# Antennas.net
KiCad netlist of a schematic drawn in Altium Designer
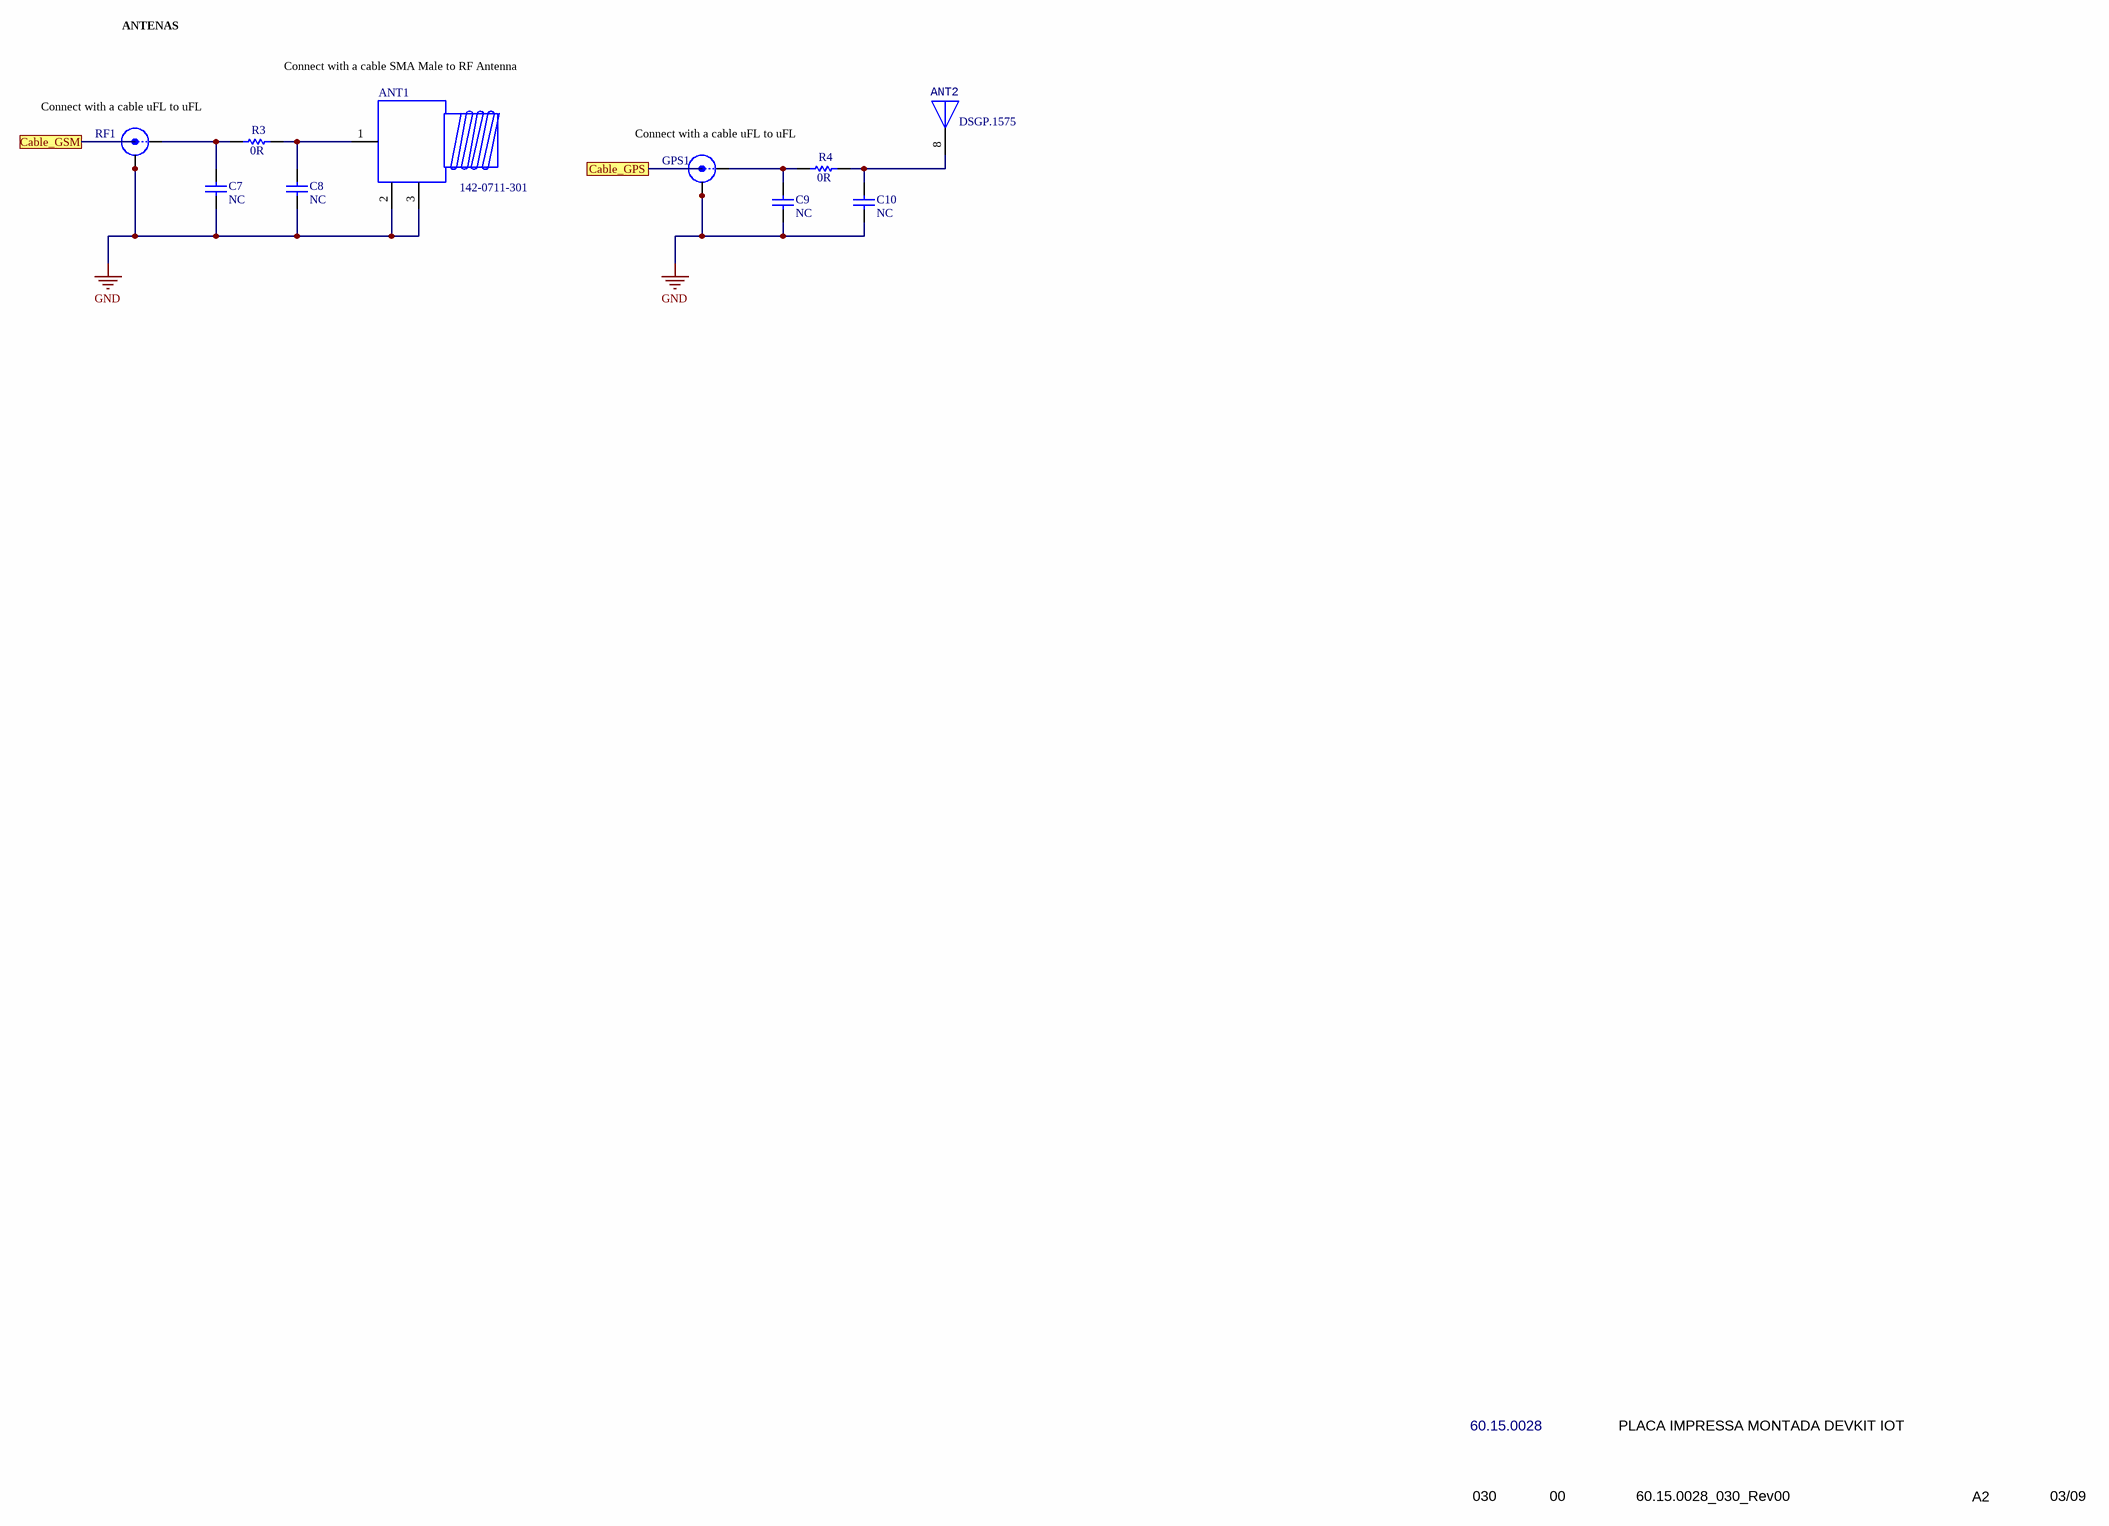
[diagram p0: Antennas.SchDoc]

(export (version "E")
  (design (tool "Eeschema 10.0.6"))
  (components
    (comp (ref "ANT1")
      (value "142-0711-301")
      (footprint "28.21.0036")
      (description "CONECTOR SMA JACK R/A 50 OHM SMD")
      (fields (field (name "Comment") "28.21.0036"))
      (libsource (lib "OMNI-CONECTORES") (part "28.21.0036"))
    )
    (comp (ref "ANT2")
      (value "50.42.0045")
      (footprint "50.42.0045")
      (description "ANTENA CERAMICA SMT PARA GPSL1")
      (fields (field (name "ALTIUM_UNNAMED_1") "DSGP.1575"))
      (libsource (lib "OMNI-COMP-RF") (part "50.42.0045"))
    )
    (comp (ref "C7")
      (value "NC")
      (footprint "0603-CAP-NA")
      (description "CAPACITOR ABERTO")
      (fields (field (name "Comment") "0603-CAP-NA"))
      (libsource (lib "OMNI-SEM-COD") (part "0603-CAP-NA"))
    )
    (comp (ref "C8")
      (value "NC")
      (footprint "0603-CAP-NA")
      (description "CAPACITOR ABERTO")
      (fields (field (name "Comment") "0603-CAP-NA"))
      (libsource (lib "OMNI-SEM-COD") (part "0603-CAP-NA"))
    )
    (comp (ref "C9")
      (value "NC")
      (footprint "0603-CAP-NA")
      (description "CAPACITOR ABERTO")
      (fields (field (name "Comment") "0603-CAP-NA"))
      (libsource (lib "OMNI-SEM-COD") (part "0603-CAP-NA"))
    )
    (comp (ref "C10")
      (value "NC")
      (footprint "0603-CAP-NA")
      (description "CAPACITOR ABERTO")
      (fields (field (name "Comment") "0603-CAP-NA"))
      (libsource (lib "OMNI-SEM-COD") (part "0603-CAP-NA"))
    )
    (comp (ref "GPS1")
      (value "28.20.0019")
      (footprint "28.20.0019")
      (description "CONECTOR MICRO COAXIAL 50 OHM SMD")
      (libsource (lib "OMNI-CONECTORES") (part "28.20.0019"))
    )
    (comp (ref "R3")
      (value "0R")
      (footprint "66.24.1337")
      (description "RESISTOR THICK FILM 0,1W 0 OHMS SMD 0603")
      (fields (field (name "Comment") "66.24.1337"))
      (libsource (lib "OMNI-RESISTORES") (part "66.24.1337"))
    )
    (comp (ref "R4")
      (value "0R")
      (footprint "66.24.1337")
      (description "RESISTOR THICK FILM 0,1W 0 OHMS SMD 0603")
      (fields (field (name "Comment") "66.24.1337"))
      (libsource (lib "OMNI-RESISTORES") (part "66.24.1337"))
    )
    (comp (ref "RF1")
      (value "28.20.0019")
      (footprint "28.20.0019")
      (description "CONECTOR MICRO COAXIAL 50 OHM SMD")
      (libsource (lib "OMNI-CONECTORES") (part "28.20.0019"))
    )
  )
  (nets
    (net (code "3") (name "GND") (class "Default")
      (node (ref "ANT1") (pin "2") (pinfunction "2_2") (pintype "passive"))
      (node (ref "ANT1") (pin "3") (pinfunction "3_3") (pintype "passive"))
      (node (ref "C10") (pin "1") (pinfunction "1_1") (pintype "passive"))
      (node (ref "C7") (pin "1") (pinfunction "1_1") (pintype "passive"))
      (node (ref "C8") (pin "1") (pinfunction "1_1") (pintype "passive"))
      (node (ref "C9") (pin "1") (pinfunction "1_1") (pintype "passive"))
      (node (ref "GPS1") (pin "2") (pinfunction "GND_2") (pintype "power_in"))
      (node (ref "GPS1") (pin "3") (pinfunction "GND_3") (pintype "power_in"))
      (node (ref "RF1") (pin "2") (pinfunction "GND_2") (pintype "power_in"))
      (node (ref "RF1") (pin "3") (pinfunction "GND_3") (pintype "power_in"))
    )
    (net (code "4") (name "Net-(ANT1-Pad1)") (class "Default")
      (node (ref "ANT1") (pin "1") (pinfunction "1_1") (pintype "passive"))
      (node (ref "C8") (pin "2") (pinfunction "2_2") (pintype "passive"))
      (node (ref "R3") (pin "2") (pinfunction "2_2") (pintype "passive"))
    )
    (net (code "5") (name "Net-(ANT2-Pad8)") (class "Default")
      (node (ref "ANT2") (pin "8") (pinfunction "8_8") (pintype "passive"))
      (node (ref "C10") (pin "2") (pinfunction "2_2") (pintype "passive"))
      (node (ref "R4") (pin "2") (pinfunction "2_2") (pintype "passive"))
    )
    (net (code "6") (name "Net-(GPS1-SIG)") (class "Default")
      (node (ref "C9") (pin "2") (pinfunction "2_2") (pintype "passive"))
      (node (ref "GPS1") (pin "1") (pinfunction "SIG_1") (pintype "passive"))
      (node (ref "R4") (pin "1") (pinfunction "1_1") (pintype "passive"))
    )
    (net (code "7") (name "Net-(RF1-SIG)") (class "Default")
      (node (ref "C7") (pin "2") (pinfunction "2_2") (pintype "passive"))
      (node (ref "R3") (pin "1") (pinfunction "1_1") (pintype "passive"))
      (node (ref "RF1") (pin "1") (pinfunction "SIG_1") (pintype "passive"))
    )
  )
)
